# 60w.net
KiCad netlist of a schematic drawn in Altium Designer
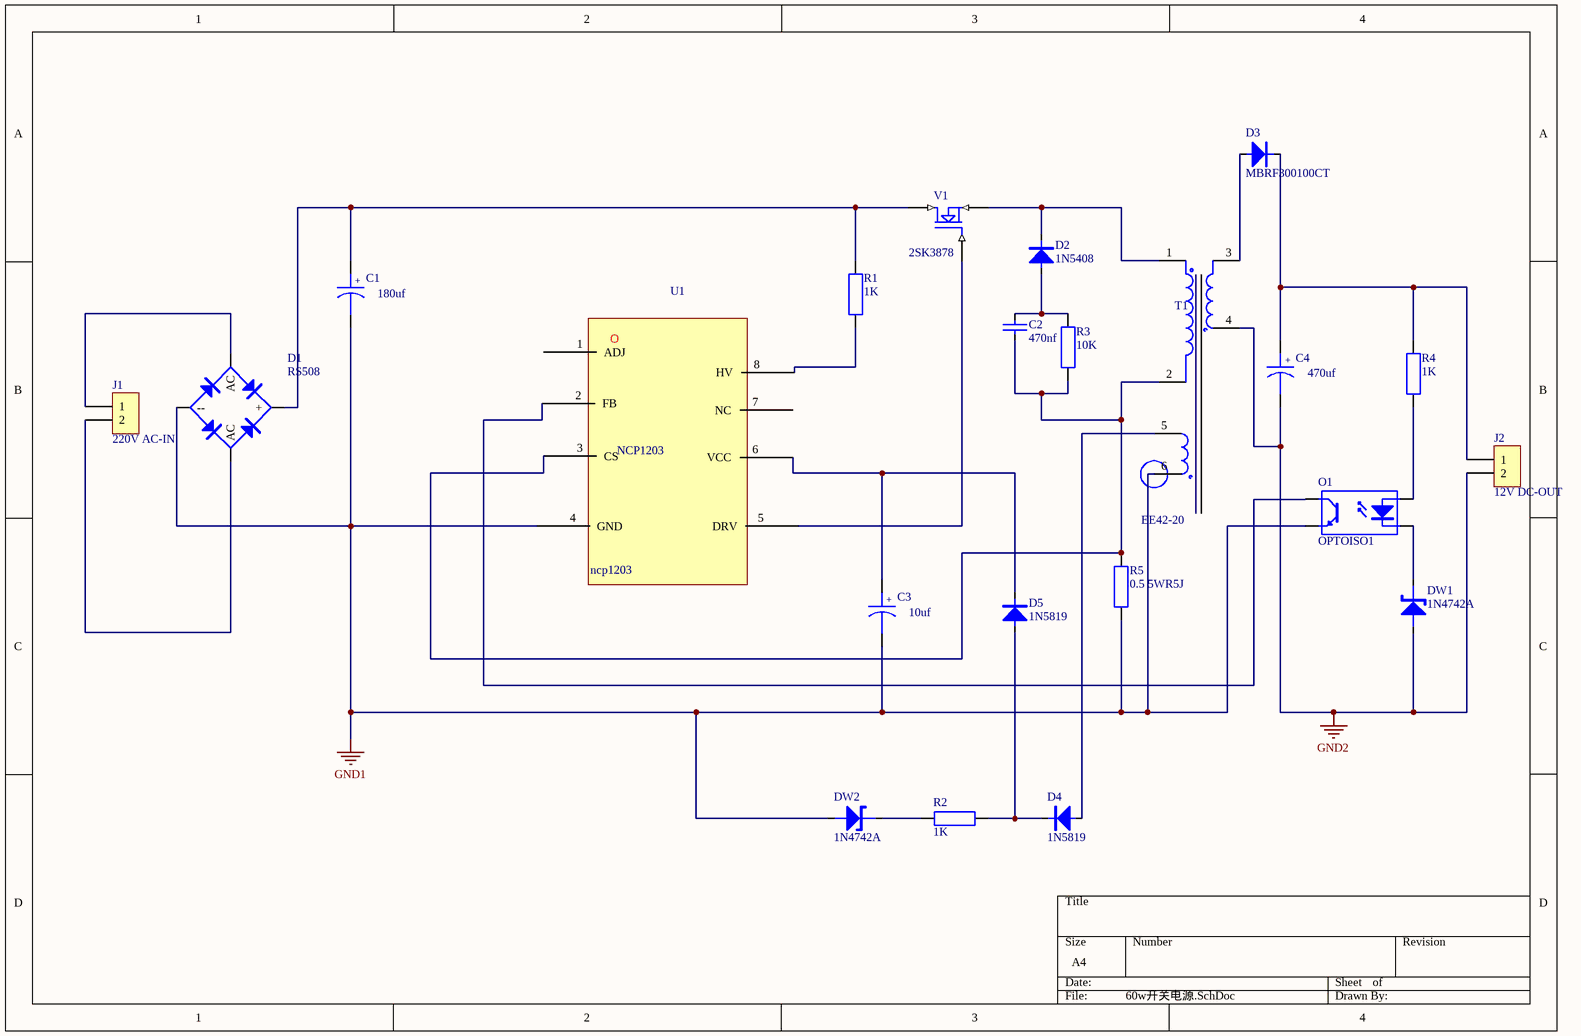
[diagram p0: 60w开关电源.SchDoc]

(export (version "E")
  (design (tool "Eeschema 10.0.6"))
  (components
    (comp (ref "C1")
      (value "180uf")
      (footprint "180uf")
      (description "Capacitor")
      (libsource (lib "杂元件库") (part "CAPACITOR POL"))
    )
    (comp (ref "C2") (value "470nf") (footprint "CAP 474J") (libsource (lib "MISCESCH") (part "CAP")))
    (comp (ref "C3")
      (value "10uf")
      (footprint "CAP_D5MM")
      (description "Capacitor")
      (libsource (lib "杂元件库") (part "CAPACITOR POL"))
    )
    (comp (ref "C4")
      (value "470uf")
      (footprint "CAP_D8MM")
      (description "Capacitor")
      (libsource (lib "杂元件库") (part "CAPACITOR POL"))
    )
    (comp (ref "D1") (value "RS508") (footprint "RS508") (libsource (lib "MISCESCH") (part "BRIDGE1")))
    (comp (ref "D2") (value "1N5408") (footprint "DO-27") (libsource (lib "MISCESCH") (part "DIODE")))
    (comp (ref "D3")
      (value "MBRF300100CT")
      (footprint "mbrf30100ct")
      (libsource (lib "MISCESCH") (part "DIODE"))
    )
    (comp (ref "D4") (value "1N5819") (footprint "DO-41") (libsource (lib "MISCESCH") (part "DIODE")))
    (comp (ref "D5") (value "1N5819") (footprint "DO-41") (libsource (lib "MISCESCH") (part "DIODE")))
    (comp (ref "DW1") (value "1N4742A") (footprint "DO-41") (libsource (lib "60w开关电源库") (part "ZENER2")))
    (comp (ref "DW2") (value "1N4742A") (footprint "do-41") (libsource (lib "60w开关电源库") (part "ZENER2")))
    (comp (ref "J1")
      (value "220V AC-IN")
      (footprint "3pin")
      (description "Connector")
      (libsource (lib "杂元件库") (part "CON2"))
    )
    (comp (ref "J2")
      (value "12V DC-OUT")
      (footprint "3PIN")
      (description "Connector")
      (libsource (lib "杂元件库") (part "CON2"))
    )
    (comp (ref "O1") (value "OPTOISO1") (footprint "PC817") (libsource (lib "60w开关电源库") (part "OPTOISO1")))
    (comp (ref "R1") (value "1K") (footprint "axial0.4") (libsource (lib "MISCESCH") (part "RES")))
    (comp (ref "R2") (value "1K") (footprint "axial0.4") (libsource (lib "MISCESCH") (part "RES")))
    (comp (ref "R3") (value "10K") (footprint "axial0.4") (libsource (lib "MISCESCH") (part "RES")))
    (comp (ref "R4") (value "1K") (footprint "axial0.4") (libsource (lib "MISCESCH") (part "RES")))
    (comp (ref "R5") (value "0.5 5WR5J") (footprint "5wr5j") (libsource (lib "MISCESCH") (part "RES")))
    (comp (ref "T1") (value "EE42-20") (footprint "ee4220") (libsource (lib "60w开关电源库") (part "变压器")))
    (comp (ref "U1") (value "ncp1203") (footprint "NCP1203") (libsource (lib "60w开关电源库") (part "ncp1203")))
    (comp (ref "V1") (value "2SK3878") (footprint "to-3p") (libsource (lib "MISCESCH") (part "MOSFET N")))
  )
  (nets
    (net (code "1") (name "GND1") (class "Default")
      (node (ref "C1") (pin "2") (pinfunction "2_2") (pintype "passive"))
      (node (ref "C3") (pin "2") (pinfunction "2_2") (pintype "passive"))
      (node (ref "D1") (pin "4") (pinfunction "--_4") (pintype "passive"))
      (node (ref "DW2") (pin "1") (pintype "passive"))
      (node (ref "O1") (pin "3") (pintype "passive"))
      (node (ref "R5") (pin "1") (pinfunction "1_1") (pintype "passive"))
      (node (ref "T1") (pin "6") (pinfunction "sec+_6") (pintype "passive"))
      (node (ref "U1") (pin "4") (pinfunction "GND_4") (pintype "passive"))
    )
    (net (code "2") (name "GND2") (class "Default")
      (node (ref "C4") (pin "2") (pinfunction "2_2") (pintype "passive"))
      (node (ref "DW1") (pin "1") (pintype "passive"))
      (node (ref "J2") (pin "2") (pinfunction "2_2") (pintype "passive"))
      (node (ref "T1") (pin "4") (pinfunction "Sec+_4") (pintype "passive"))
    )
    (net (code "3") (name "Net-(C2-Pad1)") (class "Default")
      (node (ref "C2") (pin "1") (pintype "passive"))
      (node (ref "D2") (pin "1") (pinfunction "1_1") (pintype "passive"))
      (node (ref "R3") (pin "2") (pinfunction "2_2") (pintype "passive"))
    )
    (net (code "4") (name "Net-(C4-Pad1)") (class "Default")
      (node (ref "C4") (pin "1") (pinfunction "1_1") (pintype "passive"))
      (node (ref "D3") (pin "2") (pinfunction "2_2") (pintype "passive"))
      (node (ref "J2") (pin "1") (pinfunction "1_1") (pintype "passive"))
      (node (ref "R4") (pin "2") (pinfunction "2_2") (pintype "passive"))
    )
    (net (code "5") (name "Net-(D1-+)") (class "Default")
      (node (ref "C1") (pin "1") (pinfunction "1_1") (pintype "passive"))
      (node (ref "D1") (pin "1") (pinfunction "+_1") (pintype "passive"))
      (node (ref "R1") (pin "2") (pinfunction "2_2") (pintype "passive"))
      (node (ref "V1") (pin "2") (pinfunction "D_2") (pintype "input"))
    )
    (net (code "6") (name "Net-(D1-AC-Pad2)") (class "Default")
      (node (ref "D1") (pin "2") (pinfunction "AC_2") (pintype "passive"))
      (node (ref "J1") (pin "1") (pinfunction "1_1") (pintype "passive"))
    )
    (net (code "7") (name "Net-(D1-AC-Pad3)") (class "Default")
      (node (ref "D1") (pin "3") (pinfunction "AC_3") (pintype "passive"))
      (node (ref "J1") (pin "2") (pinfunction "2_2") (pintype "passive"))
    )
    (net (code "8") (name "Net-(D4-Pad2)") (class "Default")
      (node (ref "D4") (pin "2") (pinfunction "2_2") (pintype "passive"))
      (node (ref "D5") (pin "1") (pinfunction "1_1") (pintype "passive"))
      (node (ref "R2") (pin "1") (pinfunction "1_1") (pintype "passive"))
    )
    (net (code "9") (name "Net-(DW1-Pad2)") (class "Default")
      (node (ref "DW1") (pin "2") (pintype "passive"))
      (node (ref "O1") (pin "2") (pintype "passive"))
    )
    (net (code "10") (name "Net-(DW2-Pad2)") (class "Default")
      (node (ref "DW2") (pin "2") (pintype "passive"))
      (node (ref "R2") (pin "2") (pinfunction "2_2") (pintype "passive"))
    )
    (net (code "11") (name "Net-(O1-Pad1)") (class "Default")
      (node (ref "O1") (pin "1") (pintype "passive"))
      (node (ref "R4") (pin "1") (pinfunction "1_1") (pintype "passive"))
    )
    (net (code "12") (name "Net-(T1-Pri+)") (class "Default")
      (node (ref "D2") (pin "2") (pinfunction "2_2") (pintype "passive"))
      (node (ref "T1") (pin "1") (pinfunction "Pri+_1") (pintype "passive"))
      (node (ref "V1") (pin "3") (pinfunction "S_3") (pintype "input"))
    )
    (net (code "13") (name "Net-(T1-Pri-)") (class "Default")
      (node (ref "C2") (pin "2") (pintype "passive"))
      (node (ref "R3") (pin "1") (pinfunction "1_1") (pintype "passive"))
      (node (ref "R5") (pin "2") (pinfunction "2_2") (pintype "passive"))
      (node (ref "T1") (pin "2") (pinfunction "Pri-_2") (pintype "passive"))
      (node (ref "U1") (pin "3") (pinfunction "CS_3") (pintype "passive"))
    )
    (net (code "14") (name "Net-(T1-Sec-)") (class "Default")
      (node (ref "D3") (pin "1") (pinfunction "1_1") (pintype "passive"))
      (node (ref "T1") (pin "3") (pinfunction "Sec-_3") (pintype "passive"))
    )
    (net (code "15") (name "Net-(T1-sec-)") (class "Default")
      (node (ref "D4") (pin "1") (pinfunction "1_1") (pintype "passive"))
      (node (ref "T1") (pin "5") (pinfunction "sec-_5") (pintype "passive"))
    )
    (net (code "16") (name "Net-(U1-DRV)") (class "Default")
      (node (ref "U1") (pin "5") (pinfunction "DRV_5") (pintype "passive"))
      (node (ref "V1") (pin "1") (pinfunction "G_1") (pintype "input"))
    )
    (net (code "17") (name "Net-(U1-FB)") (class "Default")
      (node (ref "O1") (pin "4") (pintype "passive"))
      (node (ref "U1") (pin "2") (pinfunction "FB_2") (pintype "passive"))
    )
    (net (code "18") (name "Net-(U1-HV)") (class "Default")
      (node (ref "R1") (pin "1") (pinfunction "1_1") (pintype "passive"))
      (node (ref "U1") (pin "8") (pinfunction "HV_8") (pintype "passive"))
    )
    (net (code "19") (name "Net-(U1-VCC)") (class "Default")
      (node (ref "C3") (pin "1") (pinfunction "1_1") (pintype "passive"))
      (node (ref "D5") (pin "2") (pinfunction "2_2") (pintype "passive"))
      (node (ref "U1") (pin "6") (pinfunction "VCC_6") (pintype "passive"))
    )
    (net (code "20") (name "unconnected-(U1-ADJ-Pad1)") (class "Default")
      (node (ref "U1") (pin "1") (pinfunction "ADJ_1") (pintype "passive"))
    )
    (net (code "21") (name "unconnected-(U1-NC-Pad7)") (class "Default")
      (node (ref "U1") (pin "7") (pinfunction "NC_7") (pintype "passive"))
    )
  )
)
